# WirelessPCB-Micro.net
KiCad netlist of a schematic drawn in Altium Designer
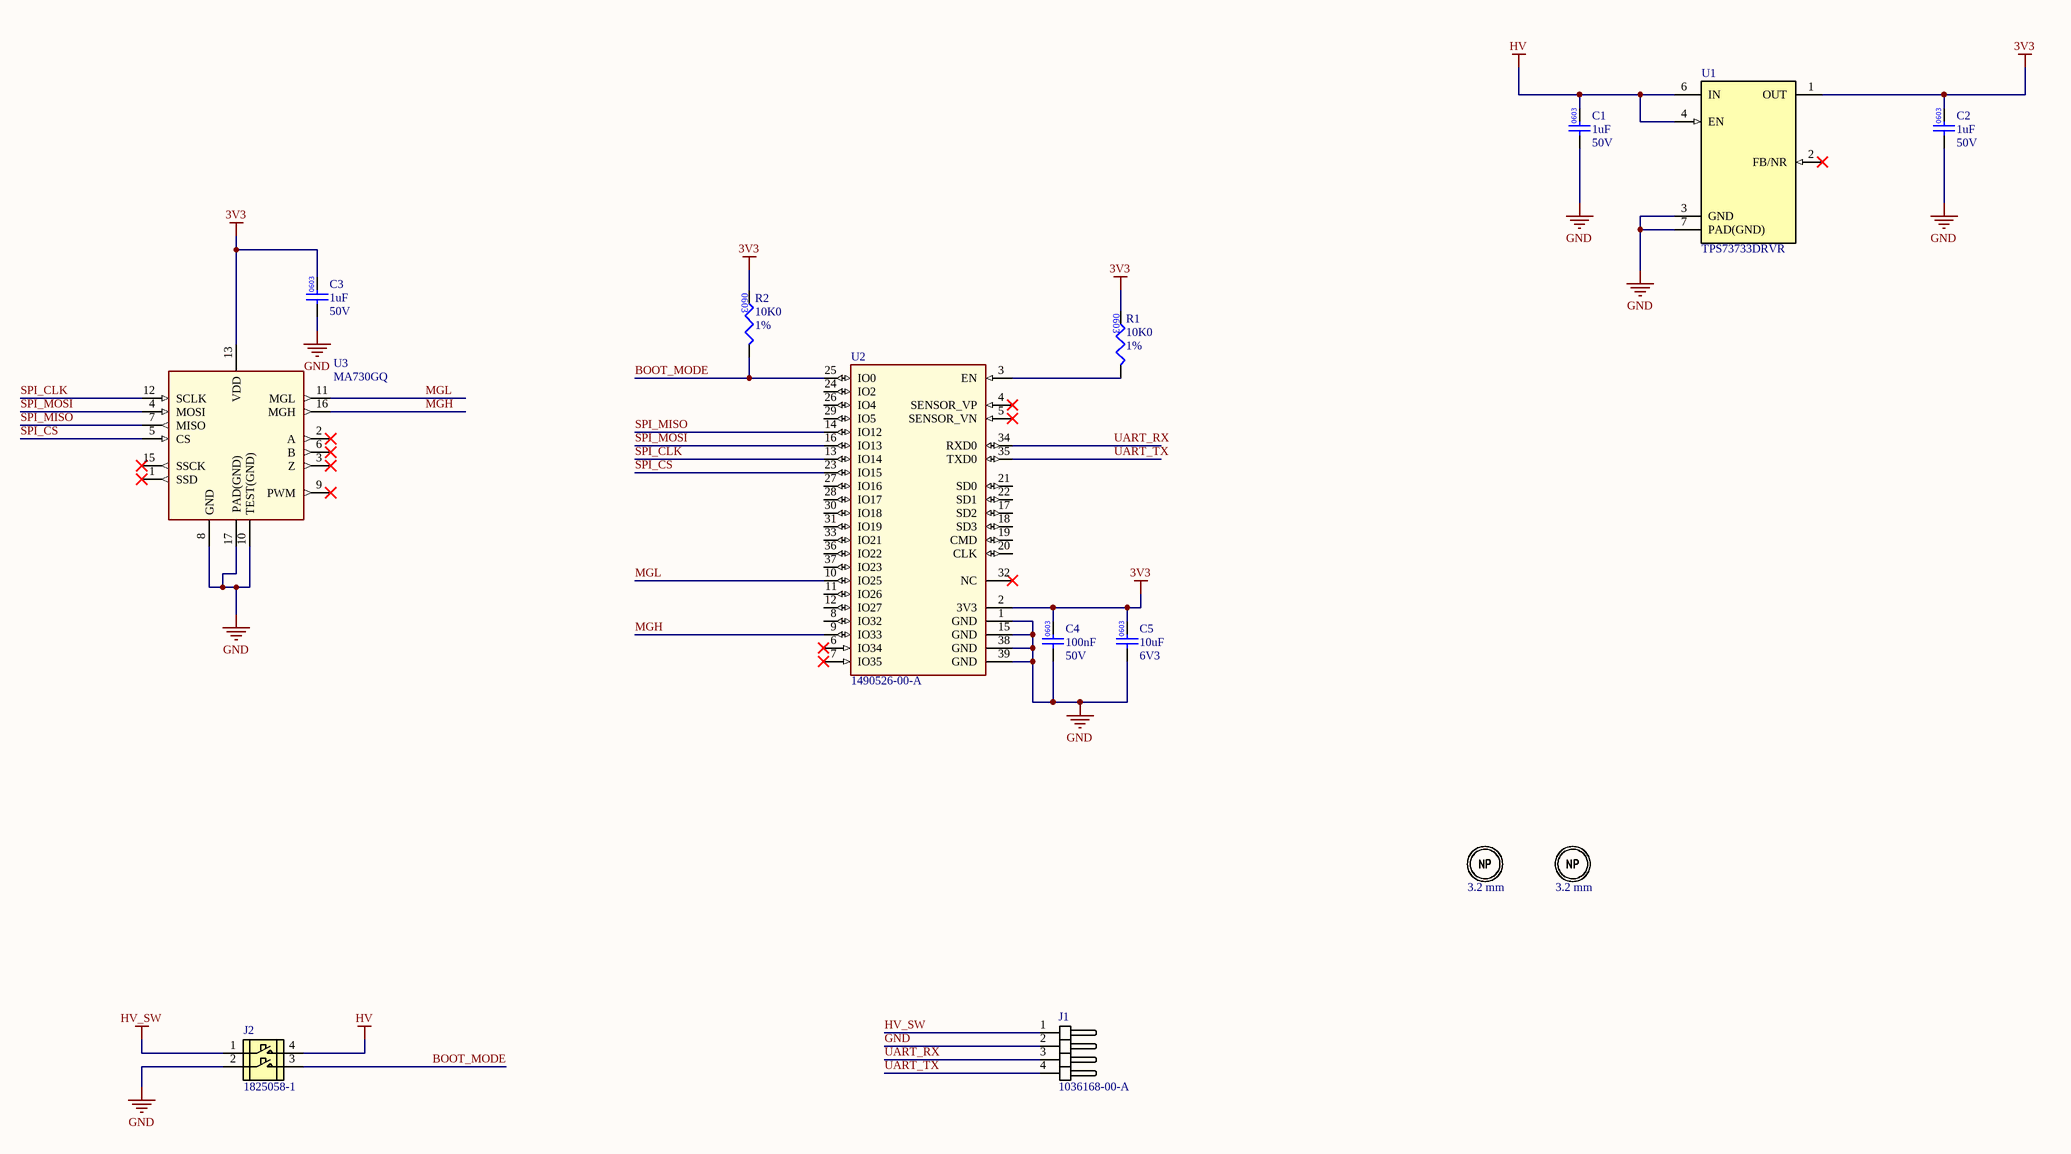
[diagram p0: WirelessPCB-Micro.SchDoc]

(export (version "E")
  (design (tool "Eeschema 10.0.6"))
  (components
    (comp (ref "C1")
      (value "1uF")
      (footprint "CAPC1608X80N")
      (description "CAPACITOR 0603(1608) 1uF X5R 50V  [AEC-Q]")
      (fields
        (field (name "PART NUMBER") "1034454-00-A")
        (field (name "VOLTAGE") "50V")
        (field (name "MANUFACTURER") "TDK")
      )
      (libsource (lib "Altium Vault") (part "CAPACITOR_0603_(1608)"))
    )
    (comp (ref "C2")
      (value "1uF")
      (footprint "CAPC1608X80N")
      (description "CAPACITOR 0603(1608) 1uF X5R 50V  [AEC-Q]")
      (fields
        (field (name "PART NUMBER") "1034454-00-A")
        (field (name "VOLTAGE") "50V")
        (field (name "MANUFACTURER") "TDK")
      )
      (libsource (lib "Altium Vault") (part "CAPACITOR_0603_(1608)"))
    )
    (comp (ref "C3")
      (value "1uF")
      (footprint "CAPC1608X80N")
      (description "CAPACITOR 0603(1608) 1uF X5R 50V  [AEC-Q]")
      (fields
        (field (name "PART NUMBER") "1034454-00-A")
        (field (name "VOLTAGE") "50V")
        (field (name "MANUFACTURER") "TDK")
      )
      (libsource (lib "Altium Vault") (part "CAPACITOR_0603_(1608)"))
    )
    (comp (ref "C4")
      (value "100nF")
      (footprint "CAPC1608X80N")
      (description "CAP,X5R,0.47UF,50V,10%,0603(1608)")
      (fields
        (field (name "PART NUMBER") "2005100")
        (field (name "VOLTAGE") "50V")
        (field (name "MANUFACTURER") "MURATA")
      )
      (libsource (lib "Altium Vault") (part "CAPACITOR_0603_(1608)"))
    )
    (comp (ref "C5")
      (value "10uF")
      (footprint "CAPC1608X80N")
      (description "CAPACITOR 0603(1608) 10uF X5R 6V3  [AEC-Q]")
      (fields
        (field (name "PART NUMBER") "1054400-00-A")
        (field (name "VOLTAGE") "6V3")
        (field (name "MANUFACTURER") "KEMET")
      )
      (libsource (lib "Altium Vault") (part "CAPACITOR_0603_(1608)"))
    )
    (comp (ref "J1")
      (value "1036168-00-A")
      (footprint "MOLEX_22-28-4043")
      (description "HEADER BREAKABLE 1X4 PINS GOLD FLASH")
      (fields (field (name "MANUFACTURER PARTNO") "22-28-4043") (field (name "MANUFACTURER") "MOLEX"))
      (libsource (lib "Altium Vault") (part "CON_MOLEX_22-28-4043"))
    )
    (comp (ref "J2")
      (value "1115379-00-A")
      (footprint "SWITCH-TE-1825058-1")
      (description "SW,DIP,SPST,2POS,0.1A,24VDC,SM")
      (fields (field (name "MANUFACTURER") "TE") (field (name "MANUFACTURER PARTNO") "1825058-1"))
      (libsource (lib "Altium Vault") (part "DIPSWITCH-2"))
    )
    (comp (ref "M1")
      (value "MOUNTING HOLE UNPLATED 3.2 MM")
      (footprint "MTG320")
      (fields (field (name "DIAMETER") "3.2 mm") (field (name "PART NUMBER") "BOARD_FEATURE"))
      (libsource (lib "Altium Vault") (part "MOUNTING_HOLE_NON_PLATED"))
    )
    (comp (ref "M2")
      (value "MOUNTING HOLE UNPLATED 3.2 MM")
      (footprint "MTG320")
      (fields (field (name "DIAMETER") "3.2 mm") (field (name "PART NUMBER") "BOARD_FEATURE"))
      (libsource (lib "Altium Vault") (part "MOUNTING_HOLE_NON_PLATED"))
    )
    (comp (ref "R1")
      (value "10K0")
      (footprint "RESC1608X50N")
      (description "RESISTOR 0603(1608) 10K0 1% 1/10W")
      (fields
        (field (name "PART NUMBER") "2000015")
        (field (name "TOLERANCE") "1%")
        (field (name "MANUFACTURER PARTNO") "CRCW06031002FKTA")
      )
      (libsource (lib "Altium Vault") (part "RESISTOR_0603_(1608)"))
    )
    (comp (ref "R2")
      (value "10K0")
      (footprint "RESC1608X50N")
      (description "RESISTOR 0603(1608) 10K0 1% 1/10W")
      (fields
        (field (name "PART NUMBER") "2000015")
        (field (name "TOLERANCE") "1%")
        (field (name "MANUFACTURER PARTNO") "CRCW06031002FKTA")
      )
      (libsource (lib "Altium Vault") (part "RESISTOR_0603_(1608)"))
    )
    (comp (ref "U1")
      (value "1517151-00-A")
      (footprint "SON65P200X200X80-7AN")
      (description "IC,VOLT-REG,LDO,3.3V,1A,WSON6,AEC-Q")
      (fields
        (field (name "MANUFACTURER") "Texas Instruments")
        (field (name "MANUFACTURER PARTNO") "TPS73733DRVR")
      )
      (libsource (lib "Altium Vault") (part "IC-TI-TPS73733-WSON6"))
    )
    (comp (ref "U2")
      (value "1490526-00-A")
      (footprint "MODULE-ESPRESSIF-ESP32-WROOM-32")
      (description "MODULE,WIFI/BLE,150MBPS,ESP32,SMD-38")
      (fields
        (field (name "MANUFACTURER") "Espressif Systems")
        (field (name "MANUFACTURER PARTNO") "ESP32-WROOM-32")
      )
      (libsource (lib "Altium Vault") (part "MODULE-ESPRESSIF-ESP32-WROOM-32"))
    )
    (comp (ref "U3")
      (value "1483744-00-A")
      (footprint "QFN50P300X300X100_HS-17N")
      (description "IC,ANGLE SNSR,14-BIT,MA730,QFN16")
      (fields (field (name "MANUFACTURER") "MPS") (field (name "MANUFACTURER PARTNO") "MA730GQ"))
      (libsource (lib "Altium Vault") (part "IC-MPS-MA730GQ"))
    )
  )
  (nets
    (net (code "1") (name "/BOOT_MODE") (class "Default")
      (node (ref "J2") (pin "3") (pinfunction "3_3") (pintype "passive"))
      (node (ref "R2") (pin "2") (pinfunction "2_2") (pintype "passive"))
      (node (ref "U2") (pin "25") (pinfunction "IO0_25") (pintype "bidirectional"))
    )
    (net (code "2") (name "/MGH") (class "Default")
      (node (ref "U2") (pin "9") (pinfunction "IO33_9") (pintype "bidirectional"))
      (node (ref "U3") (pin "16") (pinfunction "MGH_16") (pintype "output"))
    )
    (net (code "3") (name "/MGL") (class "Default")
      (node (ref "U2") (pin "10") (pinfunction "IO25_10") (pintype "bidirectional"))
      (node (ref "U3") (pin "11") (pinfunction "MGL_11") (pintype "output"))
    )
    (net (code "4") (name "/SPI_CLK") (class "Default")
      (node (ref "U2") (pin "13") (pinfunction "IO14_13") (pintype "bidirectional"))
      (node (ref "U3") (pin "12") (pinfunction "SCLK_12") (pintype "input"))
    )
    (net (code "5") (name "/SPI_CS") (class "Default")
      (node (ref "U2") (pin "23") (pinfunction "IO15_23") (pintype "bidirectional"))
      (node (ref "U3") (pin "5") (pinfunction "CS_5") (pintype "input"))
    )
    (net (code "6") (name "/SPI_MISO") (class "Default")
      (node (ref "U2") (pin "14") (pinfunction "IO12_14") (pintype "bidirectional"))
      (node (ref "U3") (pin "7") (pinfunction "MISO_7") (pintype "output"))
    )
    (net (code "7") (name "/SPI_MOSI") (class "Default")
      (node (ref "U2") (pin "16") (pinfunction "IO13_16") (pintype "bidirectional"))
      (node (ref "U3") (pin "4") (pinfunction "MOSI_4") (pintype "input"))
    )
    (net (code "8") (name "/UART_RX") (class "Default")
      (node (ref "J1") (pin "3") (pinfunction "3_3") (pintype "passive"))
      (node (ref "U2") (pin "34") (pinfunction "RXD0_34") (pintype "bidirectional"))
    )
    (net (code "9") (name "/UART_TX") (class "Default")
      (node (ref "J1") (pin "4") (pinfunction "4_4") (pintype "passive"))
      (node (ref "U2") (pin "35") (pinfunction "TXD0_35") (pintype "bidirectional"))
    )
    (net (code "10") (name "3V3") (class "Default")
      (node (ref "C2") (pin "1") (pinfunction "1_1") (pintype "passive"))
      (node (ref "C3") (pin "1") (pinfunction "1_1") (pintype "passive"))
      (node (ref "C4") (pin "1") (pinfunction "1_1") (pintype "passive"))
      (node (ref "C5") (pin "1") (pinfunction "1_1") (pintype "passive"))
      (node (ref "R1") (pin "1") (pinfunction "1_1") (pintype "passive"))
      (node (ref "R2") (pin "1") (pinfunction "1_1") (pintype "passive"))
      (node (ref "U1") (pin "1") (pinfunction "OUT_1") (pintype "passive"))
      (node (ref "U2") (pin "2") (pinfunction "3V3_2") (pintype "power_in"))
      (node (ref "U3") (pin "13") (pinfunction "VDD_13") (pintype "power_in"))
    )
    (net (code "11") (name "GND") (class "Default")
      (node (ref "C1") (pin "2") (pinfunction "2_2") (pintype "passive"))
      (node (ref "C2") (pin "2") (pinfunction "2_2") (pintype "passive"))
      (node (ref "C3") (pin "2") (pinfunction "2_2") (pintype "passive"))
      (node (ref "C4") (pin "2") (pinfunction "2_2") (pintype "passive"))
      (node (ref "C5") (pin "2") (pinfunction "2_2") (pintype "passive"))
      (node (ref "J1") (pin "2") (pinfunction "2_2") (pintype "passive"))
      (node (ref "J2") (pin "2") (pinfunction "2_2") (pintype "passive"))
      (node (ref "U1") (pin "3") (pinfunction "GND_3") (pintype "power_in"))
      (node (ref "U1") (pin "7") (pinfunction "PAD(GND)_7") (pintype "power_in"))
      (node (ref "U2") (pin "1") (pinfunction "GND_1") (pintype "power_in"))
      (node (ref "U2") (pin "15") (pinfunction "GND_15") (pintype "power_in"))
      (node (ref "U2") (pin "38") (pinfunction "GND_38") (pintype "power_in"))
      (node (ref "U2") (pin "39") (pinfunction "GND_39") (pintype "power_in"))
      (node (ref "U3") (pin "10") (pinfunction "TEST(GND)_10") (pintype "power_in"))
      (node (ref "U3") (pin "17") (pinfunction "PAD(GND)_17") (pintype "power_in"))
      (node (ref "U3") (pin "8") (pinfunction "GND_8") (pintype "power_in"))
    )
    (net (code "12") (name "HV") (class "Default")
      (node (ref "C1") (pin "1") (pinfunction "1_1") (pintype "passive"))
      (node (ref "J2") (pin "4") (pinfunction "4_4") (pintype "passive"))
      (node (ref "U1") (pin "4") (pinfunction "EN_4") (pintype "input"))
      (node (ref "U1") (pin "6") (pinfunction "IN_6") (pintype "power_in"))
    )
    (net (code "13") (name "HV_SW") (class "Default")
      (node (ref "J1") (pin "1") (pinfunction "1_1") (pintype "passive"))
      (node (ref "J2") (pin "1") (pinfunction "1_1") (pintype "passive"))
    )
    (net (code "14") (name "Net-(U2-EN)") (class "Default")
      (node (ref "R1") (pin "2") (pinfunction "2_2") (pintype "passive"))
      (node (ref "U2") (pin "3") (pinfunction "EN_3") (pintype "input"))
    )
    (net (code "15") (name "unconnected-(U1-FB{slash}NR-Pad2)") (class "Default")
      (node (ref "U1") (pin "2") (pinfunction "FB/NR_2") (pintype "input+no_connect"))
    )
    (net (code "16") (name "unconnected-(U2-CLK-Pad20)") (class "Default")
      (node (ref "U2") (pin "20") (pinfunction "CLK_20") (pintype "bidirectional"))
    )
    (net (code "17") (name "unconnected-(U2-CMD-Pad19)") (class "Default")
      (node (ref "U2") (pin "19") (pinfunction "CMD_19") (pintype "bidirectional"))
    )
    (net (code "18") (name "unconnected-(U2-IO2-Pad24)") (class "Default")
      (node (ref "U2") (pin "24") (pinfunction "IO2_24") (pintype "bidirectional"))
    )
    (net (code "19") (name "unconnected-(U2-IO4-Pad26)") (class "Default")
      (node (ref "U2") (pin "26") (pinfunction "IO4_26") (pintype "bidirectional"))
    )
    (net (code "20") (name "unconnected-(U2-IO5-Pad29)") (class "Default")
      (node (ref "U2") (pin "29") (pinfunction "IO5_29") (pintype "bidirectional"))
    )
    (net (code "21") (name "unconnected-(U2-IO16-Pad27)") (class "Default")
      (node (ref "U2") (pin "27") (pinfunction "IO16_27") (pintype "bidirectional"))
    )
    (net (code "22") (name "unconnected-(U2-IO17-Pad28)") (class "Default")
      (node (ref "U2") (pin "28") (pinfunction "IO17_28") (pintype "bidirectional"))
    )
    (net (code "23") (name "unconnected-(U2-IO18-Pad30)") (class "Default")
      (node (ref "U2") (pin "30") (pinfunction "IO18_30") (pintype "bidirectional"))
    )
    (net (code "24") (name "unconnected-(U2-IO19-Pad31)") (class "Default")
      (node (ref "U2") (pin "31") (pinfunction "IO19_31") (pintype "bidirectional"))
    )
    (net (code "25") (name "unconnected-(U2-IO21-Pad33)") (class "Default")
      (node (ref "U2") (pin "33") (pinfunction "IO21_33") (pintype "bidirectional"))
    )
    (net (code "26") (name "unconnected-(U2-IO22-Pad36)") (class "Default")
      (node (ref "U2") (pin "36") (pinfunction "IO22_36") (pintype "bidirectional"))
    )
    (net (code "27") (name "unconnected-(U2-IO23-Pad37)") (class "Default")
      (node (ref "U2") (pin "37") (pinfunction "IO23_37") (pintype "bidirectional"))
    )
    (net (code "28") (name "unconnected-(U2-IO26-Pad11)") (class "Default")
      (node (ref "U2") (pin "11") (pinfunction "IO26_11") (pintype "bidirectional"))
    )
    (net (code "29") (name "unconnected-(U2-IO27-Pad12)") (class "Default")
      (node (ref "U2") (pin "12") (pinfunction "IO27_12") (pintype "bidirectional"))
    )
    (net (code "30") (name "unconnected-(U2-IO32-Pad8)") (class "Default")
      (node (ref "U2") (pin "8") (pinfunction "IO32_8") (pintype "bidirectional"))
    )
    (net (code "31") (name "unconnected-(U2-IO34-Pad6)") (class "Default")
      (node (ref "U2") (pin "6") (pinfunction "IO34_6") (pintype "input+no_connect"))
    )
    (net (code "32") (name "unconnected-(U2-IO35-Pad7)") (class "Default")
      (node (ref "U2") (pin "7") (pinfunction "IO35_7") (pintype "input+no_connect"))
    )
    (net (code "33") (name "unconnected-(U2-NC-Pad32)") (class "Default")
      (node (ref "U2") (pin "32") (pinfunction "NC_32") (pintype "passive+no_connect"))
    )
    (net (code "34") (name "unconnected-(U2-SD0-Pad21)") (class "Default")
      (node (ref "U2") (pin "21") (pinfunction "SD0_21") (pintype "bidirectional"))
    )
    (net (code "35") (name "unconnected-(U2-SD1-Pad22)") (class "Default")
      (node (ref "U2") (pin "22") (pinfunction "SD1_22") (pintype "bidirectional"))
    )
    (net (code "36") (name "unconnected-(U2-SD2-Pad17)") (class "Default")
      (node (ref "U2") (pin "17") (pinfunction "SD2_17") (pintype "bidirectional"))
    )
    (net (code "37") (name "unconnected-(U2-SD3-Pad18)") (class "Default")
      (node (ref "U2") (pin "18") (pinfunction "SD3_18") (pintype "bidirectional"))
    )
    (net (code "38") (name "unconnected-(U2-SENSOR_VN-Pad5)") (class "Default")
      (node (ref "U2") (pin "5") (pinfunction "SENSOR_VN_5") (pintype "input+no_connect"))
    )
    (net (code "39") (name "unconnected-(U2-SENSOR_VP-Pad4)") (class "Default")
      (node (ref "U2") (pin "4") (pinfunction "SENSOR_VP_4") (pintype "input+no_connect"))
    )
    (net (code "40") (name "unconnected-(U3-A-Pad2)") (class "Default")
      (node (ref "U3") (pin "2") (pinfunction "A_2") (pintype "output+no_connect"))
    )
    (net (code "41") (name "unconnected-(U3-B-Pad6)") (class "Default")
      (node (ref "U3") (pin "6") (pinfunction "B_6") (pintype "output+no_connect"))
    )
    (net (code "42") (name "unconnected-(U3-PWM-Pad9)") (class "Default")
      (node (ref "U3") (pin "9") (pinfunction "PWM_9") (pintype "output+no_connect"))
    )
    (net (code "43") (name "unconnected-(U3-SSCK-Pad15)") (class "Default")
      (node (ref "U3") (pin "15") (pinfunction "SSCK_15") (pintype "output+no_connect"))
    )
    (net (code "44") (name "unconnected-(U3-SSD-Pad1)") (class "Default")
      (node (ref "U3") (pin "1") (pinfunction "SSD_1") (pintype "output+no_connect"))
    )
    (net (code "45") (name "unconnected-(U3-Z-Pad3)") (class "Default")
      (node (ref "U3") (pin "3") (pinfunction "Z_3") (pintype "output+no_connect"))
    )
  )
)
